# TCS32X0.net
KiCad netlist of a schematic drawn in EAGLE
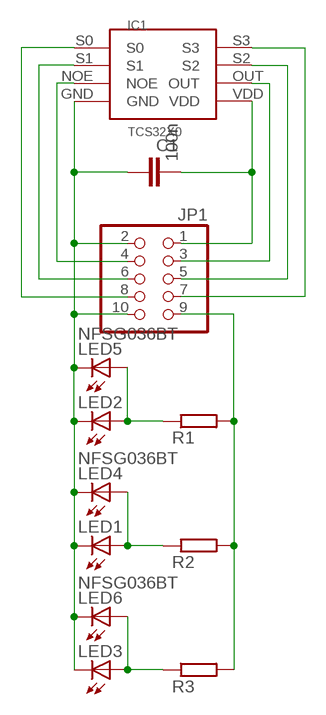
[diagram p0: schematic, sheet 1]

(export (version "E")
  (design (tool "Eeschema 10.0.6"))
  (components
    (comp (ref "C1")
      (value "100n")
      (footprint "eagle-import:C0805")
      (libsource (lib "eagle-import") (part "C-EUC0805"))
    )
    (comp (ref "IC1")
      (value "TCS32X0")
      (footprint "eagle-import:TCS32X0")
      (libsource (lib "eagle-import") (part "TCS32X0"))
    )
    (comp (ref "JP1")
      (value "PINHD-2X5")
      (footprint "eagle-import:2X05")
      (libsource (lib "eagle-import") (part "PINHD-2X5"))
    )
    (comp (ref "LED1")
      (value "LED3MM")
      (footprint "eagle-import:LED3MM")
      (libsource (lib "eagle-import") (part "LED3MM"))
    )
    (comp (ref "LED2")
      (value "LED3MM")
      (footprint "eagle-import:LED3MM")
      (libsource (lib "eagle-import") (part "LED3MM"))
    )
    (comp (ref "LED3")
      (value "LED3MM")
      (footprint "eagle-import:LED3MM")
      (libsource (lib "eagle-import") (part "LED3MM"))
    )
    (comp (ref "LED4")
      (value "NFSG036BT")
      (footprint "eagle-import:NFSG036BT")
      (libsource (lib "eagle-import") (part "NFSG036BT"))
    )
    (comp (ref "LED5")
      (value "NFSG036BT")
      (footprint "eagle-import:NFSG036BT")
      (libsource (lib "eagle-import") (part "NFSG036BT"))
    )
    (comp (ref "LED6")
      (value "NFSG036BT")
      (footprint "eagle-import:NFSG036BT")
      (libsource (lib "eagle-import") (part "NFSG036BT"))
    )
    (comp (ref "R1")
      (value "R-EU_M0805")
      (footprint "eagle-import:M0805")
      (libsource (lib "eagle-import") (part "R-EU_M0805"))
    )
    (comp (ref "R2")
      (value "R-EU_M0805")
      (footprint "eagle-import:M0805")
      (libsource (lib "eagle-import") (part "R-EU_M0805"))
    )
    (comp (ref "R3")
      (value "R-EU_M0805")
      (footprint "eagle-import:M0805")
      (libsource (lib "eagle-import") (part "R-EU_M0805"))
    )
  )
  (nets
    (net (code "1") (name "Net-(C1-Pad2)") (class "Default")
      (node (ref "C1") (pin "2") (pinfunction "2_2") (pintype "passive"))
      (node (ref "IC1") (pin "VDD") (pinfunction "VDD_VDD") (pintype "power_in"))
      (node (ref "JP1") (pin "1") (pinfunction "1_1") (pintype "passive"))
    )
    (net (code "2") (name "Net-(IC1-PadNOE)") (class "Default")
      (node (ref "IC1") (pin "NOE") (pinfunction "NOE_NOE") (pintype "output"))
      (node (ref "JP1") (pin "4") (pinfunction "4_4") (pintype "passive"))
    )
    (net (code "3") (name "Net-(IC1-PadOUT)") (class "Default")
      (node (ref "IC1") (pin "OUT") (pinfunction "OUT_OUT") (pintype "output"))
      (node (ref "JP1") (pin "3") (pinfunction "3_3") (pintype "passive"))
    )
    (net (code "4") (name "Net-(IC1-PadS0)") (class "Default")
      (node (ref "IC1") (pin "S0") (pinfunction "S0_S0") (pintype "input"))
      (node (ref "JP1") (pin "8") (pinfunction "8_8") (pintype "passive"))
    )
    (net (code "5") (name "Net-(IC1-PadS1)") (class "Default")
      (node (ref "IC1") (pin "S1") (pinfunction "S1_S1") (pintype "input"))
      (node (ref "JP1") (pin "6") (pinfunction "6_6") (pintype "passive"))
    )
    (net (code "6") (name "Net-(IC1-PadS2)") (class "Default")
      (node (ref "IC1") (pin "S2") (pinfunction "S2_S2") (pintype "input"))
      (node (ref "JP1") (pin "5") (pinfunction "5_5") (pintype "passive"))
    )
    (net (code "7") (name "Net-(IC1-PadS3)") (class "Default")
      (node (ref "IC1") (pin "S3") (pinfunction "S3_S3") (pintype "input"))
      (node (ref "JP1") (pin "7") (pinfunction "7_7") (pintype "passive"))
    )
    (net (code "8") (name "Net-(JP1-Pad9)") (class "Default")
      (node (ref "JP1") (pin "9") (pinfunction "9_9") (pintype "passive"))
      (node (ref "R1") (pin "2") (pinfunction "2_2") (pintype "passive"))
      (node (ref "R2") (pin "2") (pinfunction "2_2") (pintype "passive"))
      (node (ref "R3") (pin "2") (pinfunction "2_2") (pintype "passive"))
    )
    (net (code "9") (name "Net-(LED1-C)") (class "Default")
      (node (ref "C1") (pin "1") (pinfunction "1_1") (pintype "passive"))
      (node (ref "IC1") (pin "GND") (pinfunction "GND_GND") (pintype "power_in"))
      (node (ref "JP1") (pin "10") (pinfunction "10_10") (pintype "passive"))
      (node (ref "JP1") (pin "2") (pinfunction "2_2") (pintype "passive"))
      (node (ref "LED1") (pin "K") (pinfunction "C_K") (pintype "passive"))
      (node (ref "LED2") (pin "K") (pinfunction "C_K") (pintype "passive"))
      (node (ref "LED3") (pin "K") (pinfunction "C_K") (pintype "passive"))
      (node (ref "LED4") (pin "C") (pinfunction "C_C") (pintype "passive"))
      (node (ref "LED5") (pin "C") (pinfunction "C_C") (pintype "passive"))
      (node (ref "LED6") (pin "C") (pinfunction "C_C") (pintype "passive"))
    )
    (net (code "10") (name "Net-(LED1-PadA)") (class "Default")
      (node (ref "LED1") (pin "A") (pinfunction "A_A") (pintype "passive"))
      (node (ref "LED4") (pin "A") (pinfunction "A_A") (pintype "passive"))
      (node (ref "R2") (pin "1") (pinfunction "1_1") (pintype "passive"))
    )
    (net (code "11") (name "Net-(LED2-PadA)") (class "Default")
      (node (ref "LED2") (pin "A") (pinfunction "A_A") (pintype "passive"))
      (node (ref "LED5") (pin "A") (pinfunction "A_A") (pintype "passive"))
      (node (ref "R1") (pin "1") (pinfunction "1_1") (pintype "passive"))
    )
    (net (code "12") (name "Net-(LED3-PadA)") (class "Default")
      (node (ref "LED3") (pin "A") (pinfunction "A_A") (pintype "passive"))
      (node (ref "LED6") (pin "A") (pinfunction "A_A") (pintype "passive"))
      (node (ref "R3") (pin "1") (pinfunction "1_1") (pintype "passive"))
    )
  )
)
